# SH2_-_5V_VICOR_DCDC.net
KiCad netlist of a schematic drawn in Altium Designer
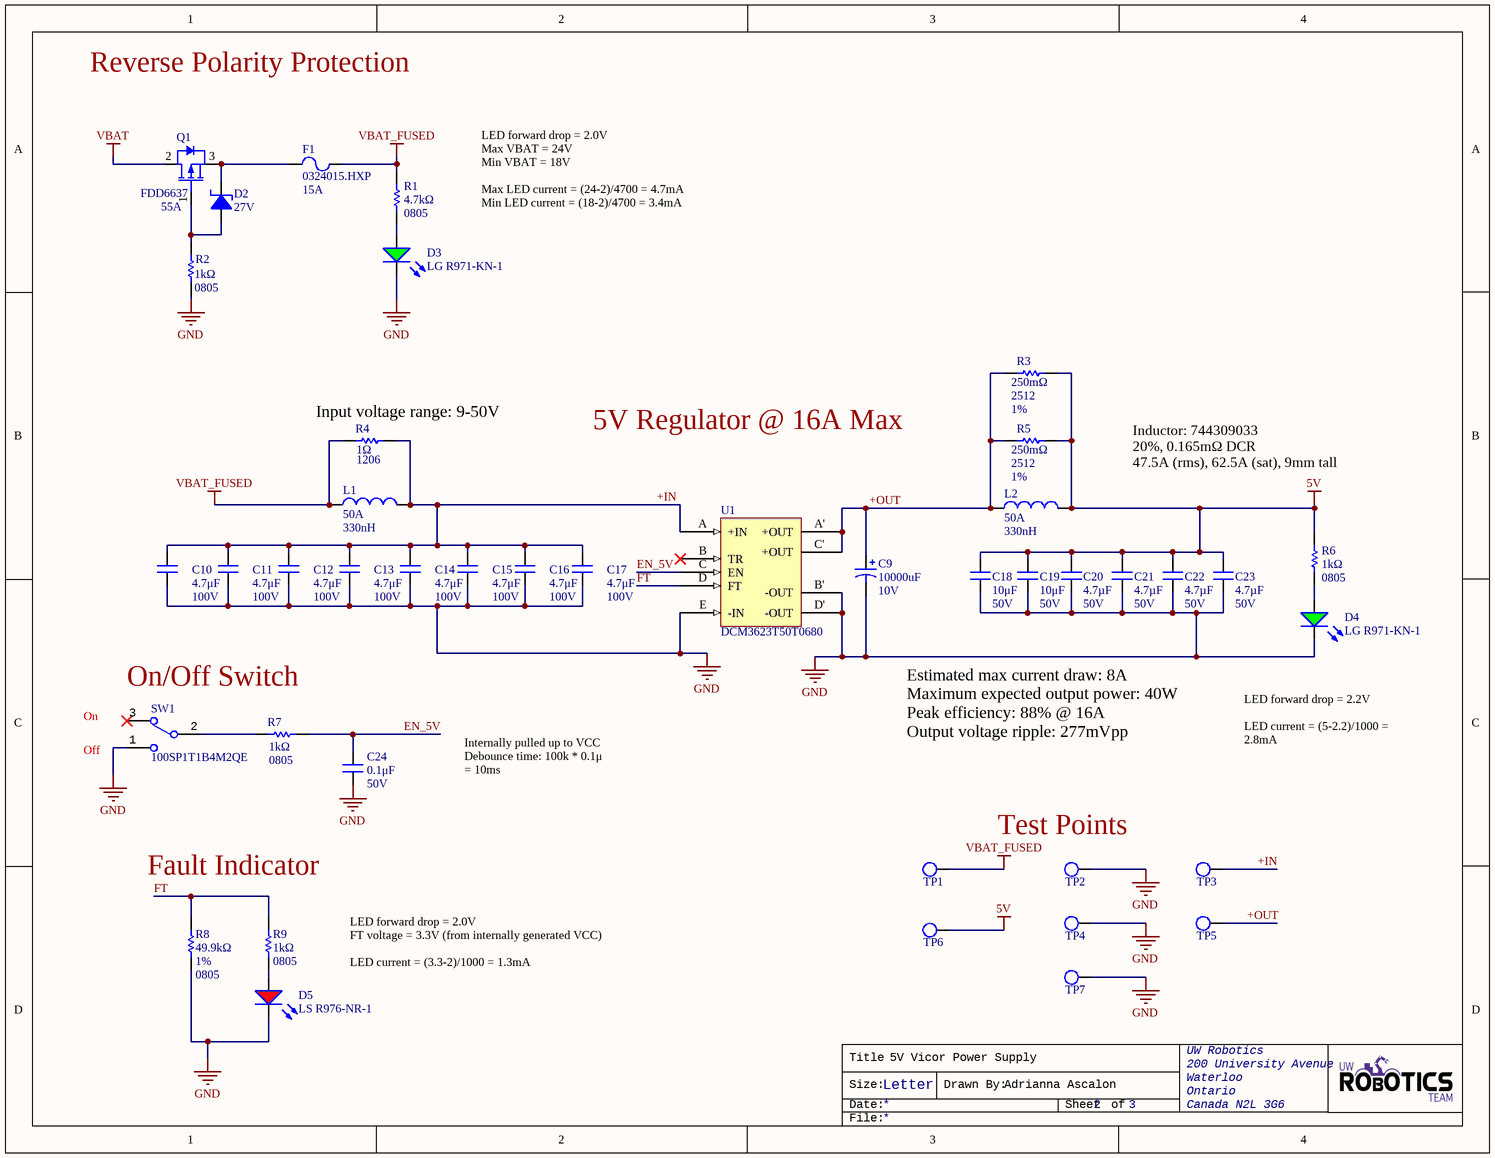
[diagram p0: SH2 - 5V VICOR DCDC.SchDoc]

(export (version "E")
  (design (tool "Eeschema 10.0.6"))
  (components
    (comp (ref "C9")
      (value "URS1A103MHD1TN")
      (footprint "CAP_UBY_18X25_NC")
      (description "CAP ALUM 10000UF 20% 10V RADIAL")
      (fields
        (field (name "TOLERANCE") "20%")
        (field (name "CAPACITANCE") "10000uF")
        (field (name "VOLTAGE RATING") "10V")
      )
      (libsource (lib "UWRT_Schematic_Library_2020") (part "URS1A103MHD1TN"))
    )
    (comp (ref "C10")
      (value "4.7μF")
      (footprint "CAPC5750X7R2A")
      (description "CAP CER 4.7UF 100V X7R 2220")
      (fields
        (field (name "MANUFACTURER") "TDK")
        (field (name "MANUFACTURER PART NUMBER") "C5750X7R2A475M230KA")
        (field (name "VOLTAGE RATING") "100V")
      )
      (libsource (lib "UWRT_Schematic_Library_2020") (part "CAP_4.7uF_100V_2220"))
    )
    (comp (ref "C11")
      (value "4.7μF")
      (footprint "CAPC5750X7R2A")
      (description "CAP CER 4.7UF 100V X7R 2220")
      (fields
        (field (name "MANUFACTURER") "TDK")
        (field (name "MANUFACTURER PART NUMBER") "C5750X7R2A475M230KA")
        (field (name "VOLTAGE RATING") "100V")
      )
      (libsource (lib "UWRT_Schematic_Library_2020") (part "CAP_4.7uF_100V_2220"))
    )
    (comp (ref "C12")
      (value "4.7μF")
      (footprint "CAPC5750X7R2A")
      (description "CAP CER 4.7UF 100V X7R 2220")
      (fields
        (field (name "MANUFACTURER") "TDK")
        (field (name "MANUFACTURER PART NUMBER") "C5750X7R2A475M230KA")
        (field (name "VOLTAGE RATING") "100V")
      )
      (libsource (lib "UWRT_Schematic_Library_2020") (part "CAP_4.7uF_100V_2220"))
    )
    (comp (ref "C13")
      (value "4.7μF")
      (footprint "CAPC5750X7R2A")
      (description "CAP CER 4.7UF 100V X7R 2220")
      (fields
        (field (name "MANUFACTURER") "TDK")
        (field (name "MANUFACTURER PART NUMBER") "C5750X7R2A475M230KA")
        (field (name "VOLTAGE RATING") "100V")
      )
      (libsource (lib "UWRT_Schematic_Library_2020") (part "CAP_4.7uF_100V_2220"))
    )
    (comp (ref "C14")
      (value "4.7μF")
      (footprint "CAPC5750X7R2A")
      (description "CAP CER 4.7UF 100V X7R 2220")
      (fields
        (field (name "MANUFACTURER") "TDK")
        (field (name "MANUFACTURER PART NUMBER") "C5750X7R2A475M230KA")
        (field (name "VOLTAGE RATING") "100V")
      )
      (libsource (lib "UWRT_Schematic_Library_2020") (part "CAP_4.7uF_100V_2220"))
    )
    (comp (ref "C15")
      (value "4.7μF")
      (footprint "CAPC5750X7R2A")
      (description "CAP CER 4.7UF 100V X7R 2220")
      (fields
        (field (name "MANUFACTURER") "TDK")
        (field (name "MANUFACTURER PART NUMBER") "C5750X7R2A475M230KA")
        (field (name "VOLTAGE RATING") "100V")
      )
      (libsource (lib "UWRT_Schematic_Library_2020") (part "CAP_4.7uF_100V_2220"))
    )
    (comp (ref "C16")
      (value "4.7μF")
      (footprint "CAPC5750X7R2A")
      (description "CAP CER 4.7UF 100V X7R 2220")
      (fields
        (field (name "MANUFACTURER") "TDK")
        (field (name "MANUFACTURER PART NUMBER") "C5750X7R2A475M230KA")
        (field (name "VOLTAGE RATING") "100V")
      )
      (libsource (lib "UWRT_Schematic_Library_2020") (part "CAP_4.7uF_100V_2220"))
    )
    (comp (ref "C17")
      (value "4.7μF")
      (footprint "CAPC5750X7R2A")
      (description "CAP CER 4.7UF 100V X7R 2220")
      (fields
        (field (name "MANUFACTURER") "TDK")
        (field (name "MANUFACTURER PART NUMBER") "C5750X7R2A475M230KA")
        (field (name "VOLTAGE RATING") "100V")
      )
      (libsource (lib "UWRT_Schematic_Library_2020") (part "CAP_4.7uF_100V_2220"))
    )
    (comp (ref "C18")
      (value "10μF")
      (footprint "CAPC1206(3216)")
      (description "CAP CER 10UF 50V X5R 1206")
      (fields (field (name "VOLTAGE RATING") "50V") (field (name "Comment") "10uF"))
      (libsource (lib "UWRT_Schematic_Library_2020") (part "CAP_10uF_50V_1206"))
    )
    (comp (ref "C19")
      (value "10μF")
      (footprint "CAPC1206(3216)")
      (description "CAP CER 10UF 50V X5R 1206")
      (fields (field (name "VOLTAGE RATING") "50V") (field (name "Comment") "10uF"))
      (libsource (lib "UWRT_Schematic_Library_2020") (part "CAP_10uF_50V_1206"))
    )
    (comp (ref "C20")
      (value "4.7µF")
      (footprint "UWRT_Footprint_Library_2020:CAPC1206(3216)")
      (description "CAP CER 4.7UF 50V X7R 1206")
      (fields (field (name "TOLERANCE") "10%") (field (name "VOLTAGE") "50V"))
      (libsource (lib "UWRT_Schematic_Library_2020") (part "CAP_4.7µF_50V_1206"))
    )
    (comp (ref "C21")
      (value "4.7µF")
      (footprint "UWRT_Footprint_Library_2020:CAPC1206(3216)")
      (description "CAP CER 4.7UF 50V X7R 1206")
      (fields (field (name "TOLERANCE") "10%") (field (name "VOLTAGE") "50V"))
      (libsource (lib "UWRT_Schematic_Library_2020") (part "CAP_4.7µF_50V_1206"))
    )
    (comp (ref "C22")
      (value "4.7µF")
      (footprint "UWRT_Footprint_Library_2020:CAPC1206(3216)")
      (description "CAP CER 4.7UF 50V X7R 1206")
      (fields (field (name "TOLERANCE") "10%") (field (name "VOLTAGE") "50V"))
      (libsource (lib "UWRT_Schematic_Library_2020") (part "CAP_4.7µF_50V_1206"))
    )
    (comp (ref "C23")
      (value "4.7µF")
      (footprint "UWRT_Footprint_Library_2020:CAPC1206(3216)")
      (description "CAP CER 4.7UF 50V X7R 1206")
      (fields (field (name "TOLERANCE") "10%") (field (name "VOLTAGE") "50V"))
      (libsource (lib "UWRT_Schematic_Library_2020") (part "CAP_4.7µF_50V_1206"))
    )
    (comp (ref "C24")
      (value "0.1μF")
      (footprint "CAPC2012X140N")
      (description "CAP CER 0.1UF 50V X7R 0805")
      (fields (field (name "VOLTAGE RATING") "50V") (field (name "TOLERANCE") "10%"))
      (libsource (lib "UWRT_Schematic_Library_2020") (part "CAP_0.1uF_50V_0805"))
    )
    (comp (ref "D2")
      (value "DIO_ZENER_27V")
      (footprint "SOT23-3")
      (description "DIODE ZENER 27V 250MW SOT23")
      (fields (field (name "TOLERANCE") "5%") (field (name "WORKING VOLTAGE") "27V"))
      (libsource (lib "UWRT_Schematic_Library_2020") (part "DIO_ZENER_27V"))
    )
    (comp (ref "D3")
      (value "LG R971-KN-1")
      (footprint "LED_0805_LINE")
      (description "LED GREEN DIFFUSED 0805 SMD")
      (fields (field (name "MANUFACTURER PART NUMBER 1") "LG R971-KN-1"))
      (libsource (lib "UWRT_Schematic_Library_2020") (part "DIO_LED_G"))
    )
    (comp (ref "D4")
      (value "LG R971-KN-1")
      (footprint "LED_0805_LINE")
      (description "LED GREEN DIFFUSED 0805 SMD")
      (libsource (lib "UWRT_Schematic_Library_2020") (part "DIO_LED_G"))
    )
    (comp (ref "D5")
      (value "LS R976-NR-1")
      (footprint "LED_0805_LINE")
      (description "LED RED DIFFUSED 0805 SMD")
      (libsource (lib "UWRT_Schematic_Library_2020") (part "DIO_LED_R"))
    )
    (comp (ref "F1")
      (value "0324015.HXP")
      (footprint "FUSE")
      (description "FUSE CERM 15A 250VAC 125VDC 3AB")
      (fields (field (name "CURRENT RATING") "15A"))
      (libsource (lib "UWRT_Schematic_Library_2020") (part "0324015.HXP"))
    )
    (comp (ref "L1")
      (value "744309033")
      (footprint "WE-HCM 1390")
      (description "IND 330NH 47.5A 0.165 MOHM")
      (fields
        (field (name "TOLERANCE") "20%")
        (field (name "MAX DC CURRENT") "50A")
        (field (name "INDUCTANCE") "330nH")
      )
      (libsource (lib "UWRT_Schematic_Library_2020") (part "744309033"))
    )
    (comp (ref "L2")
      (value "744309033")
      (footprint "WE-HCM 1390")
      (description "IND 330NH 47.5A 0.165 MOHM")
      (fields
        (field (name "TOLERANCE") "20%")
        (field (name "MAX DC CURRENT") "50A")
        (field (name "INDUCTANCE") "330nH")
      )
      (libsource (lib "UWRT_Schematic_Library_2020") (part "744309033"))
    )
    (comp (ref "Q1")
      (value "FDD6637")
      (footprint "UWRT_Footprint_Library_2020:D-PAK")
      (description "MOSFET P-CH 35V 13A DPAK")
      (fields
        (field (name "MANUFACTURER PART NUMBER 1") "FDD6637")
        (field (name "CONTINUOUS DRAIN CURRENT (ID)") "55A")
      )
      (libsource (lib "UWRT_Schematic_Library_2020") (part "FDD6637"))
    )
    (comp (ref "R1")
      (value "4.7kΩ")
      (footprint "RESC2012X60N")
      (description "RES SMD 4.7K OHM 5% 1/8W 0805")
      (fields
        (field (name "TOLERANCE") "5%")
        (field (name "CASE CODE (IMPERIAL)") "0805")
        (field (name "Comment") "RES_4.7kΩ_0805")
      )
      (libsource (lib "UWRT_Schematic_Library_2020") (part "RES_4.7kΩ_0805"))
    )
    (comp (ref "R2")
      (value "1kΩ")
      (footprint "RESC2012X60N")
      (description "RES SMD 1K OHM 1% 1/8W 0805")
      (fields (field (name "TOLERANCE") "1%") (field (name "CASE CODE (IMPERIAL)") "0805"))
      (libsource (lib "UWRT_Schematic_Library_2020") (part "RES_1kΩ_0805"))
    )
    (comp (ref "R3")
      (value "WSL2512R2500FEA")
      (footprint "RESC6432X89X76NL25T25")
      (description "RES 0.25 OHM 1% 1W 2512")
      (fields
        (field (name "MANUFACTURER") "Vishay")
        (field (name "PACKAGE REFERENCE") "2512")
        (field (name "RESISTANCE TOLERANCE") "1%")
        (field (name "RESISTANCE") "250mΩ")
      )
      (libsource (lib "UWRT_Schematic_Library_2020") (part "RES_250mΩ_2512"))
    )
    (comp (ref "R4")
      (value "RES_1Ω_1206")
      (footprint "RESC1206(3216)_N")
      (description "RES 1 OHM 5% 1/4W 1206")
      (fields
        (field (name "MANUFACTURER") "KOA Speer")
        (field (name "MANUFACTURER PART NUMBER") "RK73B2BTTE1R0J")
        (field (name "CASE CODE (IMPERIAL)") "1206")
        (field (name "RESISTANCE") "1Ω")
      )
      (libsource (lib "UWRT_Schematic_Library_2020") (part "RES_1Ω_1206"))
    )
    (comp (ref "R5")
      (value "WSL2512R2500FEA")
      (footprint "RESC6432X89X76NL25T25")
      (description "RES 0.25 OHM 1% 1W 2512")
      (fields
        (field (name "MANUFACTURER") "Vishay")
        (field (name "PACKAGE REFERENCE") "2512")
        (field (name "RESISTANCE TOLERANCE") "1%")
        (field (name "RESISTANCE") "250mΩ")
      )
      (libsource (lib "UWRT_Schematic_Library_2020") (part "RES_250mΩ_2512"))
    )
    (comp (ref "R6")
      (value "1kΩ")
      (footprint "RESC2012X60N")
      (description "RES SMD 1K OHM 1% 1/8W 0805")
      (fields (field (name "TOLERANCE") "1%") (field (name "CASE CODE (IMPERIAL)") "0805"))
      (libsource (lib "UWRT_Schematic_Library_2020") (part "RES_1kΩ_0805"))
    )
    (comp (ref "R7")
      (value "1kΩ")
      (footprint "RESC2012X60N")
      (description "RES SMD 100K OHM 0.5% 1/8W 0805")
      (fields (field (name "TOLERANCE") "0.5%") (field (name "CASE CODE (IMPERIAL)") "0805"))
      (libsource (lib "UWRT_Schematic_Library_2020") (part "RES_100kΩ_0805"))
    )
    (comp (ref "R8")
      (value "49.9kΩ")
      (footprint "RESC2012X60N")
      (description "RES SMD 49.9K OHM 1% 1/8W 0805")
      (fields (field (name "TOLERANCE") "1%") (field (name "CASE CODE (IMPERIAL)") "0805"))
      (libsource (lib "UWRT_Schematic_Library_2020") (part "RES_49.9kΩ_0805"))
    )
    (comp (ref "R9")
      (value "1kΩ")
      (footprint "RESC2012X60N")
      (description "RES SMD 1K OHM 1% 1/8W 0805")
      (fields (field (name "TOLERANCE") "1%") (field (name "CASE CODE (IMPERIAL)") "0805"))
      (libsource (lib "UWRT_Schematic_Library_2020") (part "RES_1kΩ_0805"))
    )
    (comp (ref "SW1")
      (value "100SP1T1B4M2QE")
      (footprint "100SP1T1B4M2QE")
      (description "SWITCH TOGGLE SPDT 5A 120V")
      (libsource (lib "UWRT_Schematic_Library_2020") (part "SW_SPDT"))
    )
    (comp (ref "TP1")
      (value "TESTPOINT_LOOP")
      (footprint "TESTPOINT_LOOP")
      (description "PC TEST POINT MINIATURE WHITE")
      (libsource (lib "UWRT_Schematic_Library_2020") (part "TESTPOINT_LOOP"))
    )
    (comp (ref "TP2")
      (value "TESTPOINT_LOOP")
      (footprint "TESTPOINT_LOOP")
      (description "PC TEST POINT MINIATURE WHITE")
      (libsource (lib "UWRT_Schematic_Library_2020") (part "TESTPOINT_LOOP"))
    )
    (comp (ref "TP3")
      (value "TESTPOINT_LOOP")
      (footprint "TESTPOINT_LOOP")
      (description "PC TEST POINT MINIATURE WHITE")
      (libsource (lib "UWRT_Schematic_Library_2020") (part "TESTPOINT_LOOP"))
    )
    (comp (ref "TP4")
      (value "TESTPOINT_LOOP")
      (footprint "TESTPOINT_LOOP")
      (description "PC TEST POINT MINIATURE WHITE")
      (libsource (lib "UWRT_Schematic_Library_2020") (part "TESTPOINT_LOOP"))
    )
    (comp (ref "TP5")
      (value "TESTPOINT_LOOP")
      (footprint "TESTPOINT_LOOP")
      (description "PC TEST POINT MINIATURE WHITE")
      (libsource (lib "UWRT_Schematic_Library_2020") (part "TESTPOINT_LOOP"))
    )
    (comp (ref "TP6")
      (value "TESTPOINT_LOOP")
      (footprint "TESTPOINT_LOOP")
      (description "PC TEST POINT MINIATURE WHITE")
      (libsource (lib "UWRT_Schematic_Library_2020") (part "TESTPOINT_LOOP"))
    )
    (comp (ref "TP7")
      (value "TESTPOINT_LOOP")
      (footprint "TESTPOINT_LOOP")
      (description "PC TEST POINT MINIATURE WHITE")
      (libsource (lib "UWRT_Schematic_Library_2020") (part "TESTPOINT_LOOP"))
    )
    (comp (ref "U1")
      (value "DCM3623T50T0680")
      (footprint "DCM3623T50T0680")
      (description "DC DC CONVERTER 5V 80W")
      (libsource (lib "UWRT_Schematic_Library_2020") (part "DCM3623T50T0680"))
    )
  )
  (nets
    (net (code "1") (name "/+IN") (class "Default")
      (node (ref "C10") (pin "2") (pinfunction "2_2") (pintype "passive"))
      (node (ref "C11") (pin "2") (pinfunction "2_2") (pintype "passive"))
      (node (ref "C12") (pin "2") (pinfunction "2_2") (pintype "passive"))
      (node (ref "C13") (pin "2") (pinfunction "2_2") (pintype "passive"))
      (node (ref "C14") (pin "2") (pinfunction "2_2") (pintype "passive"))
      (node (ref "C15") (pin "2") (pinfunction "2_2") (pintype "passive"))
      (node (ref "C16") (pin "2") (pinfunction "2_2") (pintype "passive"))
      (node (ref "C17") (pin "2") (pinfunction "2_2") (pintype "passive"))
      (node (ref "L1") (pin "2") (pinfunction "2_2") (pintype "passive"))
      (node (ref "R4") (pin "2") (pinfunction "2_2") (pintype "passive"))
      (node (ref "TP3") (pin "1") (pintype "passive"))
      (node (ref "U1") (pin "A") (pinfunction "+IN_A") (pintype "input"))
    )
    (net (code "2") (name "/+OUT") (class "Default")
      (node (ref "C9") (pin "1") (pinfunction "1_1") (pintype "passive"))
      (node (ref "L2") (pin "1") (pinfunction "1_1") (pintype "passive"))
      (node (ref "R3") (pin "1") (pinfunction "1_1") (pintype "passive"))
      (node (ref "R5") (pin "1") (pinfunction "1_1") (pintype "passive"))
      (node (ref "TP5") (pin "1") (pintype "passive"))
      (node (ref "U1") (pin "A'") (pinfunction "+OUT_A'") (pintype "passive"))
      (node (ref "U1") (pin "C'") (pinfunction "+OUT_C'") (pintype "passive"))
    )
    (net (code "3") (name "/EN_5V") (class "Default")
      (node (ref "C24") (pin "2") (pinfunction "2_2") (pintype "passive"))
      (node (ref "R7") (pin "2") (pinfunction "2_2") (pintype "passive"))
      (node (ref "U1") (pin "C") (pinfunction "EN_C") (pintype "input"))
    )
    (net (code "4") (name "/FT") (class "Default")
      (node (ref "R8") (pin "1") (pinfunction "1_1") (pintype "passive"))
      (node (ref "R9") (pin "2") (pinfunction "2_2") (pintype "passive"))
      (node (ref "U1") (pin "D") (pinfunction "FT_D") (pintype "input"))
    )
    (net (code "5") (name "5V") (class "Default")
      (node (ref "C18") (pin "2") (pinfunction "2_2") (pintype "passive"))
      (node (ref "C19") (pin "2") (pinfunction "2_2") (pintype "passive"))
      (node (ref "C20") (pin "2") (pinfunction "2_2") (pintype "passive"))
      (node (ref "C21") (pin "2") (pinfunction "2_2") (pintype "passive"))
      (node (ref "C22") (pin "2") (pinfunction "2_2") (pintype "passive"))
      (node (ref "C23") (pin "2") (pinfunction "2_2") (pintype "passive"))
      (node (ref "L2") (pin "2") (pinfunction "2_2") (pintype "passive"))
      (node (ref "R3") (pin "2") (pinfunction "2_2") (pintype "passive"))
      (node (ref "R5") (pin "2") (pinfunction "2_2") (pintype "passive"))
      (node (ref "R6") (pin "2") (pinfunction "2_2") (pintype "passive"))
      (node (ref "TP6") (pin "1") (pintype "passive"))
    )
    (net (code "6") (name "GND") (class "Default")
      (node (ref "C10") (pin "1") (pinfunction "1_1") (pintype "passive"))
      (node (ref "C11") (pin "1") (pinfunction "1_1") (pintype "passive"))
      (node (ref "C12") (pin "1") (pinfunction "1_1") (pintype "passive"))
      (node (ref "C13") (pin "1") (pinfunction "1_1") (pintype "passive"))
      (node (ref "C14") (pin "1") (pinfunction "1_1") (pintype "passive"))
      (node (ref "C15") (pin "1") (pinfunction "1_1") (pintype "passive"))
      (node (ref "C16") (pin "1") (pinfunction "1_1") (pintype "passive"))
      (node (ref "C17") (pin "1") (pinfunction "1_1") (pintype "passive"))
      (node (ref "C18") (pin "1") (pinfunction "1_1") (pintype "passive"))
      (node (ref "C19") (pin "1") (pinfunction "1_1") (pintype "passive"))
      (node (ref "C20") (pin "1") (pinfunction "1_1") (pintype "passive"))
      (node (ref "C21") (pin "1") (pinfunction "1_1") (pintype "passive"))
      (node (ref "C22") (pin "1") (pinfunction "1_1") (pintype "passive"))
      (node (ref "C23") (pin "1") (pinfunction "1_1") (pintype "passive"))
      (node (ref "C24") (pin "1") (pinfunction "1_1") (pintype "passive"))
      (node (ref "C9") (pin "2") (pinfunction "2_2") (pintype "passive"))
      (node (ref "D3") (pin "2") (pinfunction "K_2") (pintype "passive"))
      (node (ref "D4") (pin "2") (pinfunction "K_2") (pintype "passive"))
      (node (ref "D5") (pin "2") (pinfunction "K_2") (pintype "passive"))
      (node (ref "R2") (pin "1") (pinfunction "1_1") (pintype "passive"))
      (node (ref "R8") (pin "2") (pinfunction "2_2") (pintype "passive"))
      (node (ref "SW1") (pin "1") (pinfunction "1_1") (pintype "passive"))
      (node (ref "TP2") (pin "1") (pintype "passive"))
      (node (ref "TP4") (pin "1") (pintype "passive"))
      (node (ref "TP7") (pin "1") (pintype "passive"))
      (node (ref "U1") (pin "B'") (pinfunction "-OUT_B'") (pintype "passive"))
      (node (ref "U1") (pin "D'") (pinfunction "-OUT_D'") (pintype "passive"))
      (node (ref "U1") (pin "E") (pinfunction "-IN_E") (pintype "input"))
    )
    (net (code "7") (name "Net-(D2-Anode)") (class "Default")
      (node (ref "D2") (pin "1") (pinfunction "Anode_1") (pintype "passive"))
      (node (ref "Q1") (pin "1") (pinfunction "Gate_1") (pintype "passive"))
      (node (ref "R2") (pin "2") (pinfunction "2_2") (pintype "passive"))
    )
    (net (code "8") (name "Net-(D2-Cathode)") (class "Default")
      (node (ref "D2") (pin "2") (pinfunction "Cathode_2") (pintype "passive"))
      (node (ref "F1") (pin "1") (pinfunction "1_1") (pintype "passive"))
      (node (ref "Q1") (pin "3") (pinfunction "Source_3") (pintype "passive"))
    )
    (net (code "9") (name "Net-(D3-A)") (class "Default")
      (node (ref "D3") (pin "1") (pinfunction "A_1") (pintype "passive"))
      (node (ref "R1") (pin "1") (pinfunction "1_1") (pintype "passive"))
    )
    (net (code "10") (name "Net-(D4-A)") (class "Default")
      (node (ref "D4") (pin "1") (pinfunction "A_1") (pintype "passive"))
      (node (ref "R6") (pin "1") (pinfunction "1_1") (pintype "passive"))
    )
    (net (code "11") (name "Net-(D5-A)") (class "Default")
      (node (ref "D5") (pin "1") (pinfunction "A_1") (pintype "passive"))
      (node (ref "R9") (pin "1") (pinfunction "1_1") (pintype "passive"))
    )
    (net (code "12") (name "Net-(R7-Pad1)") (class "Default")
      (node (ref "R7") (pin "1") (pinfunction "1_1") (pintype "passive"))
      (node (ref "SW1") (pin "2") (pinfunction "2_2") (pintype "passive"))
    )
    (net (code "13") (name "VBAT") (class "Default")
      (node (ref "Q1") (pin "2") (pinfunction "Drain_2") (pintype "passive"))
    )
    (net (code "14") (name "VBAT_FUSED") (class "Default")
      (node (ref "F1") (pin "2") (pinfunction "2_2") (pintype "passive"))
      (node (ref "L1") (pin "1") (pinfunction "1_1") (pintype "passive"))
      (node (ref "R1") (pin "2") (pinfunction "2_2") (pintype "passive"))
      (node (ref "R4") (pin "1") (pinfunction "1_1") (pintype "passive"))
      (node (ref "TP1") (pin "1") (pintype "passive"))
    )
    (net (code "15") (name "unconnected-(SW1-Pad3)") (class "Default")
      (node (ref "SW1") (pin "3") (pinfunction "3_3") (pintype "passive+no_connect"))
    )
    (net (code "16") (name "unconnected-(U1-TR-PadB)") (class "Default")
      (node (ref "U1") (pin "B") (pinfunction "TR_B") (pintype "input+no_connect"))
    )
  )
)
